# Version_2_0.net
KiCad netlist of a schematic drawn in EAGLE
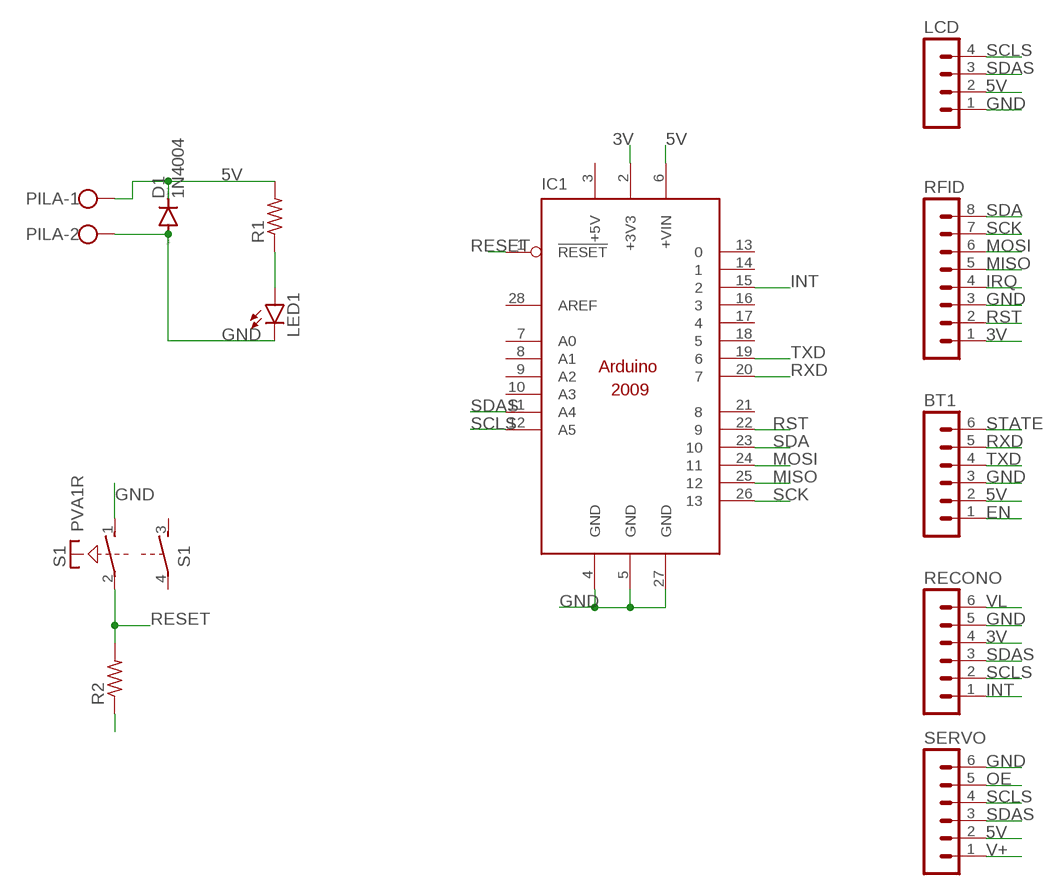
[diagram p0: schematic, sheet 1]

(export (version "E")
  (design (tool "Eeschema 10.0.6"))
  (components
    (comp (ref "BT1")
      (value "MA06-1")
      (footprint "eagle-import:MA06-1")
      (libsource (lib "eagle-import") (part "MA06-1"))
    )
    (comp (ref "D1")
      (value "1N4004")
      (footprint "eagle-import:DO41-10")
      (libsource (lib "eagle-import") (part "1N4004"))
    )
    (comp (ref "IC1")
      (value "ARDUINO2009_10")
      (footprint "eagle-import:ARDUINO2009")
      (libsource (lib "eagle-import") (part "ARDUINO2009_10"))
    )
    (comp (ref "LCD")
      (value "MA04-1")
      (footprint "eagle-import:MA04-1")
      (libsource (lib "eagle-import") (part "MA04-1"))
    )
    (comp (ref "LED1")
      (value "LED3MM")
      (footprint "eagle-import:LED3MM")
      (libsource (lib "eagle-import") (part "LED3MM"))
    )
    (comp (ref "PILA")
      (value "W237-102")
      (footprint "eagle-import:W237-102")
      (fields (field (name "MPN") "237-102"))
      (libsource (lib "eagle-import") (part "W237-102"))
    )
    (comp (ref "R1")
      (value "R-US_0204/7")
      (footprint "eagle-import:0204_7")
      (libsource (lib "eagle-import") (part "R-US_0204/7"))
    )
    (comp (ref "R2")
      (value "R-US_0204/7")
      (footprint "eagle-import:0204_7")
      (libsource (lib "eagle-import") (part "R-US_0204/7"))
    )
    (comp (ref "RECONO")
      (value "MA06-1")
      (footprint "eagle-import:MA06-1")
      (libsource (lib "eagle-import") (part "MA06-1"))
    )
    (comp (ref "RFID")
      (value "MA08-1")
      (footprint "eagle-import:MA08-1")
      (libsource (lib "eagle-import") (part "MA08-1"))
    )
    (comp (ref "S1")
      (value "PVA1R")
      (footprint "eagle-import:PVA1R")
      (libsource (lib "eagle-import") (part "PVA1R"))
    )
    (comp (ref "SERVO")
      (value "MA06-1")
      (footprint "eagle-import:MA06-1")
      (libsource (lib "eagle-import") (part "MA06-1"))
    )
  )
  (nets
    (net (code "1") (name "/+5V") (class "Default")
      (node (ref "IC1") (pin "3") (pinfunction "+5V_3") (pintype "power_in"))
    )
    (net (code "2") (name "/3V") (class "Default")
      (node (ref "IC1") (pin "2") (pinfunction "+3V3_2") (pintype "power_in"))
      (node (ref "RECONO") (pin "4") (pinfunction "4_4") (pintype "passive"))
      (node (ref "RFID") (pin "1") (pinfunction "1_1") (pintype "passive"))
    )
    (net (code "3") (name "/5V") (class "Default")
      (node (ref "BT1") (pin "2") (pinfunction "2_2") (pintype "passive"))
      (node (ref "D1") (pin "C") (pinfunction "C_C") (pintype "passive"))
      (node (ref "IC1") (pin "6") (pinfunction "+VIN_6") (pintype "bidirectional"))
      (node (ref "LCD") (pin "2") (pinfunction "2_2") (pintype "passive"))
      (node (ref "PILA") (pin "1") (pinfunction "KL_1") (pintype "passive"))
      (node (ref "R1") (pin "2") (pinfunction "2_2") (pintype "passive"))
      (node (ref "R2") (pin "1") (pinfunction "1_1") (pintype "passive"))
      (node (ref "SERVO") (pin "2") (pinfunction "2_2") (pintype "passive"))
    )
    (net (code "4") (name "/EN") (class "Default")
      (node (ref "BT1") (pin "1") (pinfunction "1_1") (pintype "passive"))
    )
    (net (code "5") (name "/GND") (class "Default")
      (node (ref "BT1") (pin "3") (pinfunction "3_3") (pintype "passive"))
      (node (ref "D1") (pin "A") (pinfunction "A_A") (pintype "passive"))
      (node (ref "IC1") (pin "27") (pinfunction "GND_27") (pintype "power_in"))
      (node (ref "IC1") (pin "4") (pinfunction "GND_4") (pintype "power_in"))
      (node (ref "IC1") (pin "5") (pinfunction "GND_5") (pintype "power_in"))
      (node (ref "LCD") (pin "1") (pinfunction "1_1") (pintype "passive"))
      (node (ref "LED1") (pin "K") (pinfunction "C_K") (pintype "passive"))
      (node (ref "PILA") (pin "2") (pinfunction "KL_2") (pintype "passive"))
      (node (ref "RECONO") (pin "5") (pinfunction "5_5") (pintype "passive"))
      (node (ref "RFID") (pin "3") (pinfunction "3_3") (pintype "passive"))
      (node (ref "S1") (pin "1") (pinfunction "S_1") (pintype "passive"))
      (node (ref "SERVO") (pin "6") (pinfunction "6_6") (pintype "passive"))
    )
    (net (code "6") (name "/INT") (class "Default")
      (node (ref "IC1") (pin "15") (pinfunction "2_15") (pintype "bidirectional"))
      (node (ref "RECONO") (pin "1") (pinfunction "1_1") (pintype "passive"))
    )
    (net (code "7") (name "/IRQ") (class "Default")
      (node (ref "RFID") (pin "4") (pinfunction "4_4") (pintype "passive"))
    )
    (net (code "8") (name "/MISO") (class "Default")
      (node (ref "IC1") (pin "25") (pinfunction "12_25") (pintype "bidirectional"))
      (node (ref "RFID") (pin "5") (pinfunction "5_5") (pintype "passive"))
    )
    (net (code "9") (name "/MOSI") (class "Default")
      (node (ref "IC1") (pin "24") (pinfunction "11_24") (pintype "bidirectional"))
      (node (ref "RFID") (pin "6") (pinfunction "6_6") (pintype "passive"))
    )
    (net (code "10") (name "/OE") (class "Default")
      (node (ref "SERVO") (pin "5") (pinfunction "5_5") (pintype "passive"))
    )
    (net (code "11") (name "/RESET") (class "Default")
      (node (ref "IC1") (pin "1") (pinfunction "~{RESET}_1") (pintype "bidirectional"))
      (node (ref "R2") (pin "2") (pinfunction "2_2") (pintype "passive"))
      (node (ref "S1") (pin "2") (pinfunction "P_2") (pintype "passive"))
    )
    (net (code "12") (name "/RST") (class "Default")
      (node (ref "IC1") (pin "22") (pinfunction "9_22") (pintype "bidirectional"))
      (node (ref "RFID") (pin "2") (pinfunction "2_2") (pintype "passive"))
    )
    (net (code "13") (name "/RXD") (class "Default")
      (node (ref "BT1") (pin "5") (pinfunction "5_5") (pintype "passive"))
      (node (ref "IC1") (pin "20") (pinfunction "7_20") (pintype "bidirectional"))
    )
    (net (code "14") (name "/SCK") (class "Default")
      (node (ref "IC1") (pin "26") (pinfunction "13_26") (pintype "bidirectional"))
      (node (ref "RFID") (pin "7") (pinfunction "7_7") (pintype "passive"))
    )
    (net (code "15") (name "/SCLS") (class "Default")
      (node (ref "IC1") (pin "12") (pinfunction "A5_12") (pintype "bidirectional"))
      (node (ref "LCD") (pin "4") (pinfunction "4_4") (pintype "passive"))
      (node (ref "RECONO") (pin "2") (pinfunction "2_2") (pintype "passive"))
      (node (ref "SERVO") (pin "4") (pinfunction "4_4") (pintype "passive"))
    )
    (net (code "16") (name "/SDA") (class "Default")
      (node (ref "IC1") (pin "23") (pinfunction "10_23") (pintype "bidirectional"))
      (node (ref "RFID") (pin "8") (pinfunction "8_8") (pintype "passive"))
    )
    (net (code "17") (name "/SDAS") (class "Default")
      (node (ref "IC1") (pin "11") (pinfunction "A4_11") (pintype "bidirectional"))
      (node (ref "LCD") (pin "3") (pinfunction "3_3") (pintype "passive"))
      (node (ref "RECONO") (pin "3") (pinfunction "3_3") (pintype "passive"))
      (node (ref "SERVO") (pin "3") (pinfunction "3_3") (pintype "passive"))
    )
    (net (code "18") (name "/STATE") (class "Default")
      (node (ref "BT1") (pin "6") (pinfunction "6_6") (pintype "passive"))
    )
    (net (code "19") (name "/TXD") (class "Default")
      (node (ref "BT1") (pin "4") (pinfunction "4_4") (pintype "passive"))
      (node (ref "IC1") (pin "19") (pinfunction "6_19") (pintype "bidirectional"))
    )
    (net (code "20") (name "/V+") (class "Default")
      (node (ref "SERVO") (pin "1") (pinfunction "1_1") (pintype "passive"))
    )
    (net (code "21") (name "/VL") (class "Default")
      (node (ref "RECONO") (pin "6") (pinfunction "6_6") (pintype "passive"))
    )
    (net (code "22") (name "Net-(LED1-PadA)") (class "Default")
      (node (ref "LED1") (pin "A") (pinfunction "A_A") (pintype "passive"))
      (node (ref "R1") (pin "1") (pinfunction "1_1") (pintype "passive"))
    )
    (net (code "23") (name "unconnected-(IC1-0-Pad13)") (class "Default")
      (node (ref "IC1") (pin "13") (pinfunction "0_13") (pintype "bidirectional"))
    )
    (net (code "24") (name "unconnected-(IC1-1-Pad14)") (class "Default")
      (node (ref "IC1") (pin "14") (pinfunction "1_14") (pintype "bidirectional"))
    )
    (net (code "25") (name "unconnected-(IC1-3-Pad16)") (class "Default")
      (node (ref "IC1") (pin "16") (pinfunction "3_16") (pintype "bidirectional"))
    )
    (net (code "26") (name "unconnected-(IC1-4-Pad17)") (class "Default")
      (node (ref "IC1") (pin "17") (pinfunction "4_17") (pintype "bidirectional"))
    )
    (net (code "27") (name "unconnected-(IC1-5-Pad18)") (class "Default")
      (node (ref "IC1") (pin "18") (pinfunction "5_18") (pintype "bidirectional"))
    )
    (net (code "28") (name "unconnected-(IC1-8-Pad21)") (class "Default")
      (node (ref "IC1") (pin "21") (pinfunction "8_21") (pintype "bidirectional"))
    )
    (net (code "29") (name "unconnected-(IC1-A0-Pad7)") (class "Default")
      (node (ref "IC1") (pin "7") (pinfunction "A0_7") (pintype "bidirectional"))
    )
    (net (code "30") (name "unconnected-(IC1-A1-Pad8)") (class "Default")
      (node (ref "IC1") (pin "8") (pinfunction "A1_8") (pintype "bidirectional"))
    )
    (net (code "31") (name "unconnected-(IC1-A2-Pad9)") (class "Default")
      (node (ref "IC1") (pin "9") (pinfunction "A2_9") (pintype "bidirectional"))
    )
    (net (code "32") (name "unconnected-(IC1-A3-Pad10)") (class "Default")
      (node (ref "IC1") (pin "10") (pinfunction "A3_10") (pintype "bidirectional"))
    )
    (net (code "33") (name "unconnected-(IC1-AREF-Pad28)") (class "Default")
      (node (ref "IC1") (pin "28") (pinfunction "AREF_28") (pintype "bidirectional"))
    )
    (net (code "34") (name "unconnected-(S1B-P-Pad4)") (class "Default")
      (node (ref "S1") (pin "4") (pinfunction "P_4") (pintype "passive"))
    )
    (net (code "35") (name "unconnected-(S1B-S-Pad3)") (class "Default")
      (node (ref "S1") (pin "3") (pinfunction "S_3") (pintype "passive"))
    )
  )
)
